# Pico.net
KiCad netlist of a schematic drawn in Altium Designer
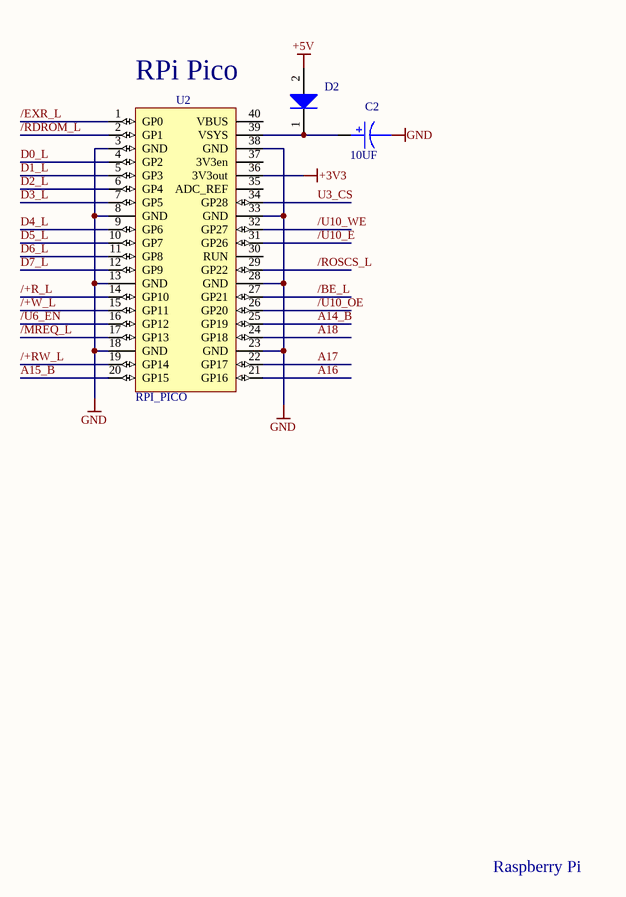
[diagram p0: Pico.SchDoc]

(export (version "E")
  (design (tool "Eeschema 10.0.6"))
  (components
    (comp (ref "C2")
      (value "10UF")
      (footprint "CAP10EL")
      (description "CAP ALUM 10UF 20% 16V RADIAL")
      (fields (field (name "MFG") "Panasonic"))
      (libsource (lib "CapacitorsTH") (part "10UF"))
    )
    (comp (ref "D2")
      (value "SB260_R2_00001")
      (footprint "DO-15")
      (description "DIODE SCHOTTKY 60V 2A DO15")
      (fields (field (name "MFG") "Panjit"))
      (libsource (lib "MiscSemi") (part "SB260_R2_00001"))
    )
    (comp (ref "U2")
      (value "RPI_PICO")
      (footprint "RPIPICO")
      (description "RASPBERRY PI PICO RP2040 BOARD")
      (fields (field (name "MFG") "Raspberry Pi"))
      (libsource (lib "Modules") (part "RPI_PICO"))
    )
  )
  (nets
    (net (code "1") (name "+3V3") (class "Default")
      (node (ref "U2") (pin "36") (pinfunction "3V3out_36") (pintype "power_in"))
    )
    (net (code "2") (name "+5V") (class "Default")
      (node (ref "D2") (pin "2") (pinfunction "A_2") (pintype "passive"))
    )
    (net (code "3") (name "/A14_B") (class "Default")
      (node (ref "U2") (pin "25") (pinfunction "GP19_25") (pintype "bidirectional"))
    )
    (net (code "4") (name "/A15_B") (class "Default")
      (node (ref "U2") (pin "20") (pinfunction "GP15_20") (pintype "bidirectional"))
    )
    (net (code "5") (name "/A16") (class "Default")
      (node (ref "U2") (pin "21") (pinfunction "GP16_21") (pintype "bidirectional"))
    )
    (net (code "6") (name "/A17") (class "Default")
      (node (ref "U2") (pin "22") (pinfunction "GP17_22") (pintype "bidirectional"))
    )
    (net (code "7") (name "/A18") (class "Default")
      (node (ref "U2") (pin "24") (pinfunction "GP18_24") (pintype "bidirectional"))
    )
    (net (code "8") (name "/D0_L") (class "Default")
      (node (ref "U2") (pin "4") (pinfunction "GP2_4") (pintype "bidirectional"))
    )
    (net (code "9") (name "/D1_L") (class "Default")
      (node (ref "U2") (pin "5") (pinfunction "GP3_5") (pintype "bidirectional"))
    )
    (net (code "10") (name "/D2_L") (class "Default")
      (node (ref "U2") (pin "6") (pinfunction "GP4_6") (pintype "bidirectional"))
    )
    (net (code "11") (name "/D3_L") (class "Default")
      (node (ref "U2") (pin "7") (pinfunction "GP5_7") (pintype "bidirectional"))
    )
    (net (code "12") (name "/D4_L") (class "Default")
      (node (ref "U2") (pin "9") (pinfunction "GP6_9") (pintype "bidirectional"))
    )
    (net (code "13") (name "/D5_L") (class "Default")
      (node (ref "U2") (pin "10") (pinfunction "GP7_10") (pintype "bidirectional"))
    )
    (net (code "14") (name "/D6_L") (class "Default")
      (node (ref "U2") (pin "11") (pinfunction "GP8_11") (pintype "bidirectional"))
    )
    (net (code "15") (name "/D7_L") (class "Default")
      (node (ref "U2") (pin "12") (pinfunction "GP9_12") (pintype "bidirectional"))
    )
    (net (code "16") (name "/U3_CS") (class "Default")
      (node (ref "U2") (pin "34") (pinfunction "GP28_34") (pintype "bidirectional"))
    )
    (net (code "17") (name "/{slash}+RW_L") (class "Default")
      (node (ref "U2") (pin "19") (pinfunction "GP14_19") (pintype "bidirectional"))
    )
    (net (code "18") (name "/{slash}+R_L") (class "Default")
      (node (ref "U2") (pin "14") (pinfunction "GP10_14") (pintype "bidirectional"))
    )
    (net (code "19") (name "/{slash}+W_L") (class "Default")
      (node (ref "U2") (pin "15") (pinfunction "GP11_15") (pintype "bidirectional"))
    )
    (net (code "20") (name "/{slash}BE_L") (class "Default")
      (node (ref "U2") (pin "27") (pinfunction "GP21_27") (pintype "bidirectional"))
    )
    (net (code "21") (name "/{slash}EXR_L") (class "Default")
      (node (ref "U2") (pin "1") (pinfunction "GP0_1") (pintype "bidirectional"))
    )
    (net (code "22") (name "/{slash}MREQ_L") (class "Default")
      (node (ref "U2") (pin "17") (pinfunction "GP13_17") (pintype "bidirectional"))
    )
    (net (code "23") (name "/{slash}RDROM_L") (class "Default")
      (node (ref "U2") (pin "2") (pinfunction "GP1_2") (pintype "bidirectional"))
    )
    (net (code "24") (name "/{slash}ROSCS_L") (class "Default")
      (node (ref "U2") (pin "29") (pinfunction "GP22_29") (pintype "bidirectional"))
    )
    (net (code "25") (name "/{slash}U6_EN") (class "Default")
      (node (ref "U2") (pin "16") (pinfunction "GP12_16") (pintype "bidirectional"))
    )
    (net (code "26") (name "/{slash}U10_E") (class "Default")
      (node (ref "U2") (pin "31") (pinfunction "GP26_31") (pintype "bidirectional"))
    )
    (net (code "27") (name "/{slash}U10_OE") (class "Default")
      (node (ref "U2") (pin "26") (pinfunction "GP20_26") (pintype "bidirectional"))
    )
    (net (code "28") (name "/{slash}U10_WE") (class "Default")
      (node (ref "U2") (pin "32") (pinfunction "GP27_32") (pintype "bidirectional"))
    )
    (net (code "29") (name "GND") (class "Default")
      (node (ref "C2") (pin "2") (pinfunction "2_2") (pintype "passive"))
      (node (ref "U2") (pin "13") (pinfunction "GND_13") (pintype "power_in"))
      (node (ref "U2") (pin "18") (pinfunction "GND_18") (pintype "power_in"))
      (node (ref "U2") (pin "23") (pinfunction "GND_23") (pintype "power_in"))
      (node (ref "U2") (pin "28") (pinfunction "GND_28") (pintype "power_in"))
      (node (ref "U2") (pin "3") (pinfunction "GND_3") (pintype "bidirectional"))
      (node (ref "U2") (pin "33") (pinfunction "GND_33") (pintype "power_in"))
      (node (ref "U2") (pin "38") (pinfunction "GND_38") (pintype "power_in"))
      (node (ref "U2") (pin "8") (pinfunction "GND_8") (pintype "power_in"))
    )
    (net (code "30") (name "Net-(U2-VSYS)") (class "Default")
      (node (ref "C2") (pin "1") (pinfunction "1_1") (pintype "passive"))
      (node (ref "D2") (pin "1") (pintype "passive"))
      (node (ref "U2") (pin "39") (pinfunction "VSYS_39") (pintype "power_in"))
    )
    (net (code "31") (name "unconnected-(U2-3V3en-Pad37)") (class "Default")
      (node (ref "U2") (pin "37") (pinfunction "3V3en_37") (pintype "passive"))
    )
    (net (code "32") (name "unconnected-(U2-ADC_REF-Pad35)") (class "Default")
      (node (ref "U2") (pin "35") (pinfunction "ADC_REF_35") (pintype "passive"))
    )
    (net (code "33") (name "unconnected-(U2-RUN-Pad30)") (class "Default")
      (node (ref "U2") (pin "30") (pinfunction "RUN_30") (pintype "passive"))
    )
    (net (code "34") (name "unconnected-(U2-VBUS-Pad40)") (class "Default")
      (node (ref "U2") (pin "40") (pinfunction "VBUS_40") (pintype "power_in"))
    )
  )
)
